# FabEEG_v5.net
KiCad netlist of a schematic drawn in EAGLE
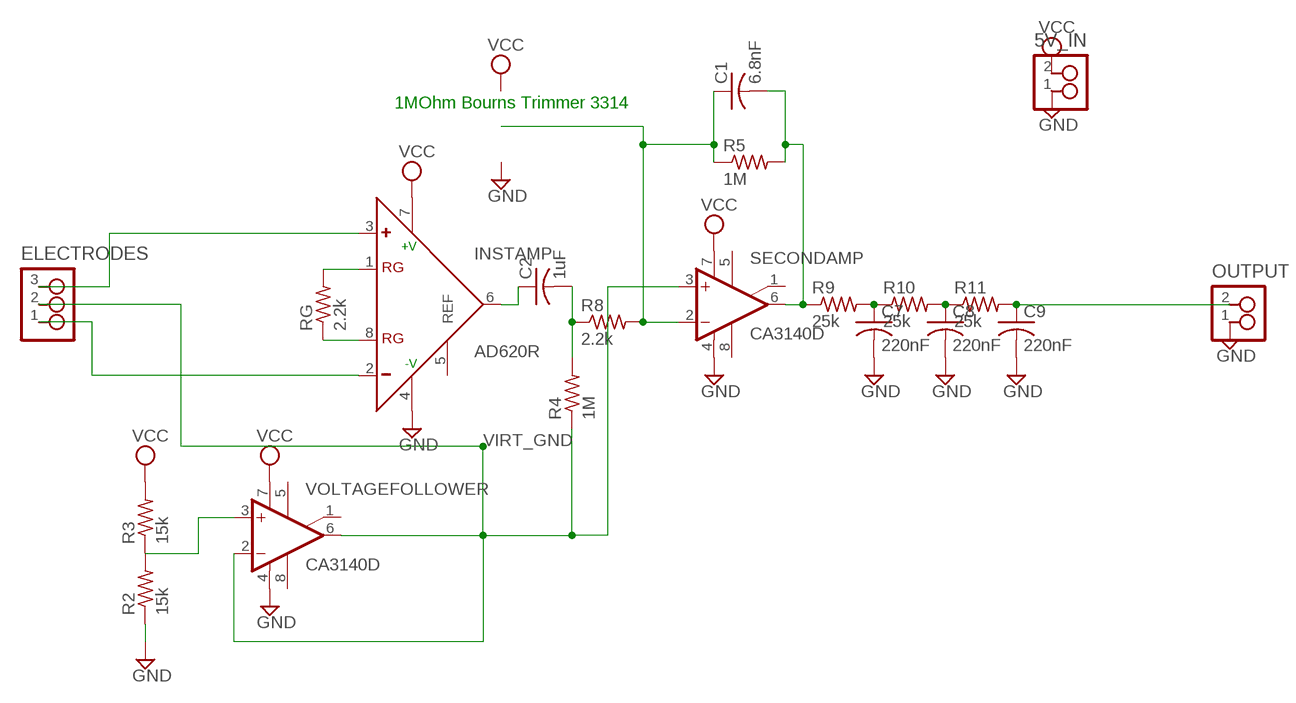
[diagram p0: schematic, sheet 1]

(export (version "E")
  (design (tool "Eeschema 10.0.6"))
  (components
    (comp (ref "5V_IN")
      (value "2_PIN_HEADERHEADER")
      (footprint "eagle-import:SMT_PINS_2")
      (libsource (lib "eagle-import") (part "2_PIN_HEADERHEADER"))
    )
    (comp (ref "C1")
      (value "6.8nF")
      (footprint "eagle-import:C1206")
      (libsource (lib "eagle-import") (part "C-USC1206"))
    )
    (comp (ref "C2")
      (value "1uF")
      (footprint "eagle-import:C1206")
      (libsource (lib "eagle-import") (part "C-USC1206"))
    )
    (comp (ref "C7")
      (value "220nF")
      (footprint "eagle-import:C1206")
      (libsource (lib "eagle-import") (part "C-USC1206"))
    )
    (comp (ref "C8")
      (value "220nF")
      (footprint "eagle-import:C1206")
      (libsource (lib "eagle-import") (part "C-USC1206"))
    )
    (comp (ref "C9")
      (value "220nF")
      (footprint "eagle-import:C1206")
      (libsource (lib "eagle-import") (part "C-USC1206"))
    )
    (comp (ref "ELECTRODES")
      (value "3_PIN_HEADERHEADER")
      (footprint "eagle-import:SMT_PINS_3")
      (libsource (lib "eagle-import") (part "3_PIN_HEADERHEADER"))
    )
    (comp (ref "INSTAMP")
      (value "AD620R")
      (footprint "eagle-import:SO8")
      (libsource (lib "eagle-import") (part "AD620R"))
    )
    (comp (ref "OUTPUT")
      (value "2_PIN_HEADERHEADER")
      (footprint "eagle-import:SMT_PINS_2")
      (libsource (lib "eagle-import") (part "2_PIN_HEADERHEADER"))
    )
    (comp (ref "R2")
      (value "15k")
      (footprint "eagle-import:R1206")
      (libsource (lib "eagle-import") (part "R-US_R1206"))
    )
    (comp (ref "R3")
      (value "15k")
      (footprint "eagle-import:R1206")
      (libsource (lib "eagle-import") (part "R-US_R1206"))
    )
    (comp (ref "R4")
      (value "1M")
      (footprint "eagle-import:R1206")
      (libsource (lib "eagle-import") (part "R-US_R1206"))
    )
    (comp (ref "R5")
      (value "1M")
      (footprint "eagle-import:R1206")
      (libsource (lib "eagle-import") (part "R-US_R1206"))
    )
    (comp (ref "R8")
      (value "2.2k")
      (footprint "eagle-import:R1206")
      (libsource (lib "eagle-import") (part "R-US_R1206"))
    )
    (comp (ref "R9")
      (value "25k")
      (footprint "eagle-import:R1206")
      (libsource (lib "eagle-import") (part "R-US_R1206"))
    )
    (comp (ref "R10")
      (value "25k")
      (footprint "eagle-import:R1206")
      (libsource (lib "eagle-import") (part "R-US_R1206"))
    )
    (comp (ref "R11")
      (value "25k")
      (footprint "eagle-import:R1206")
      (libsource (lib "eagle-import") (part "R-US_R1206"))
    )
    (comp (ref "RG")
      (value "2.2k")
      (footprint "eagle-import:R1206")
      (libsource (lib "eagle-import") (part "R-US_R1206"))
    )
    (comp (ref "SECONDAMP")
      (value "CA3140D")
      (footprint "eagle-import:SO08")
      (libsource (lib "eagle-import") (part "CA3140D"))
    )
    (comp (ref "VOLTAGEFOLLOWER")
      (value "CA3140D")
      (footprint "eagle-import:SO08")
      (libsource (lib "eagle-import") (part "CA3140D"))
    )
  )
  (nets
    (net (code "1") (name "/VIRT_GND") (class "Default")
      (node (ref "ELECTRODES") (pin "2") (pinfunction "P$2_2") (pintype "bidirectional"))
      (node (ref "R4") (pin "1") (pinfunction "1_1") (pintype "passive"))
      (node (ref "SECONDAMP") (pin "3") (pinfunction "+IN_3") (pintype "input"))
      (node (ref "VOLTAGEFOLLOWER") (pin "2") (pinfunction "-IN_2") (pintype "input"))
      (node (ref "VOLTAGEFOLLOWER") (pin "6") (pinfunction "OUT_6") (pintype "output"))
    )
    (net (code "2") (name "GND") (class "Default")
      (node (ref "5V_IN") (pin "1") (pinfunction "1_1") (pintype "bidirectional"))
      (node (ref "C7") (pin "2") (pinfunction "2_2") (pintype "passive"))
      (node (ref "C8") (pin "2") (pinfunction "2_2") (pintype "passive"))
      (node (ref "C9") (pin "2") (pinfunction "2_2") (pintype "passive"))
      (node (ref "INSTAMP") (pin "4") (pinfunction "-V_4") (pintype "power_in"))
      (node (ref "OUTPUT") (pin "1") (pinfunction "1_1") (pintype "bidirectional"))
      (node (ref "R2") (pin "1") (pinfunction "1_1") (pintype "passive"))
      (node (ref "SECONDAMP") (pin "4") (pinfunction "V-_4") (pintype "power_in"))
      (node (ref "VOLTAGEFOLLOWER") (pin "4") (pinfunction "V-_4") (pintype "power_in"))
    )
    (net (code "3") (name "Net-(C2-Pad2)") (class "Default")
      (node (ref "C2") (pin "2") (pinfunction "2_2") (pintype "passive"))
      (node (ref "R4") (pin "2") (pinfunction "2_2") (pintype "passive"))
      (node (ref "R8") (pin "1") (pinfunction "1_1") (pintype "passive"))
    )
    (net (code "4") (name "Net-(C7-Pad1)") (class "Default")
      (node (ref "C7") (pin "1") (pinfunction "1_1") (pintype "passive"))
      (node (ref "R10") (pin "1") (pinfunction "1_1") (pintype "passive"))
      (node (ref "R9") (pin "2") (pinfunction "2_2") (pintype "passive"))
    )
    (net (code "5") (name "Net-(C8-Pad1)") (class "Default")
      (node (ref "C8") (pin "1") (pinfunction "1_1") (pintype "passive"))
      (node (ref "R10") (pin "2") (pinfunction "2_2") (pintype "passive"))
      (node (ref "R11") (pin "1") (pinfunction "1_1") (pintype "passive"))
    )
    (net (code "6") (name "Net-(C9-Pad1)") (class "Default")
      (node (ref "C9") (pin "1") (pinfunction "1_1") (pintype "passive"))
      (node (ref "OUTPUT") (pin "2") (pinfunction "2_2") (pintype "bidirectional"))
      (node (ref "R11") (pin "2") (pinfunction "2_2") (pintype "passive"))
    )
    (net (code "7") (name "Net-(ELECTRODES-P$1)") (class "Default")
      (node (ref "ELECTRODES") (pin "1") (pinfunction "P$1_1") (pintype "bidirectional"))
      (node (ref "INSTAMP") (pin "2") (pinfunction "-_2") (pintype "input"))
    )
    (net (code "8") (name "Net-(ELECTRODES-P$3)") (class "Default")
      (node (ref "ELECTRODES") (pin "3") (pinfunction "P$3_3") (pintype "bidirectional"))
      (node (ref "INSTAMP") (pin "3") (pinfunction "+_3") (pintype "input"))
    )
    (net (code "9") (name "Net-(INSTAMP-OUT)") (class "Default")
      (node (ref "C2") (pin "1") (pinfunction "1_1") (pintype "passive"))
      (node (ref "INSTAMP") (pin "6") (pinfunction "OUT_6") (pintype "output"))
    )
    (net (code "10") (name "Net-(INSTAMP-RG-Pad1)") (class "Default")
      (node (ref "INSTAMP") (pin "1") (pinfunction "RG_1") (pintype "passive"))
      (node (ref "RG") (pin "2") (pinfunction "2_2") (pintype "passive"))
    )
    (net (code "11") (name "Net-(INSTAMP-RG-Pad8)") (class "Default")
      (node (ref "INSTAMP") (pin "8") (pinfunction "RG_8") (pintype "passive"))
      (node (ref "RG") (pin "1") (pinfunction "1_1") (pintype "passive"))
    )
    (net (code "12") (name "Net-(SECONDAMP--IN)") (class "Default")
      (node (ref "C1") (pin "1") (pinfunction "1_1") (pintype "passive"))
      (node (ref "R5") (pin "1") (pinfunction "1_1") (pintype "passive"))
      (node (ref "R8") (pin "2") (pinfunction "2_2") (pintype "passive"))
      (node (ref "SECONDAMP") (pin "2") (pinfunction "-IN_2") (pintype "input"))
    )
    (net (code "13") (name "Net-(SECONDAMP-OUT)") (class "Default")
      (node (ref "C1") (pin "2") (pinfunction "2_2") (pintype "passive"))
      (node (ref "R5") (pin "2") (pinfunction "2_2") (pintype "passive"))
      (node (ref "R9") (pin "1") (pinfunction "1_1") (pintype "passive"))
      (node (ref "SECONDAMP") (pin "6") (pinfunction "OUT_6") (pintype "output"))
    )
    (net (code "14") (name "Net-(VOLTAGEFOLLOWER-+IN)") (class "Default")
      (node (ref "R2") (pin "2") (pinfunction "2_2") (pintype "passive"))
      (node (ref "R3") (pin "1") (pinfunction "1_1") (pintype "passive"))
      (node (ref "VOLTAGEFOLLOWER") (pin "3") (pinfunction "+IN_3") (pintype "input"))
    )
    (net (code "15") (name "VCC") (class "Default")
      (node (ref "5V_IN") (pin "2") (pinfunction "2_2") (pintype "bidirectional"))
      (node (ref "INSTAMP") (pin "7") (pinfunction "+V_7") (pintype "power_in"))
      (node (ref "R3") (pin "2") (pinfunction "2_2") (pintype "passive"))
      (node (ref "SECONDAMP") (pin "7") (pinfunction "V+_7") (pintype "power_in"))
      (node (ref "VOLTAGEFOLLOWER") (pin "7") (pinfunction "V+_7") (pintype "power_in"))
    )
    (net (code "16") (name "unconnected-(INSTAMP-REF-Pad5)") (class "Default")
      (node (ref "INSTAMP") (pin "5") (pinfunction "REF_5") (pintype "passive"))
    )
    (net (code "17") (name "unconnected-(SECONDAMP-CMP-Pad8)") (class "Default")
      (node (ref "SECONDAMP") (pin "8") (pinfunction "CMP_8") (pintype "passive"))
    )
    (net (code "18") (name "unconnected-(SECONDAMP-ON-Pad5)") (class "Default")
      (node (ref "SECONDAMP") (pin "5") (pinfunction "ON_5") (pintype "passive"))
    )
    (net (code "19") (name "unconnected-(SECONDAMP-ON{slash}CMP-Pad1)") (class "Default")
      (node (ref "SECONDAMP") (pin "1") (pinfunction "ON/CMP_1") (pintype "passive"))
    )
    (net (code "20") (name "unconnected-(VOLTAGEFOLLOWER-CMP-Pad8)") (class "Default")
      (node (ref "VOLTAGEFOLLOWER") (pin "8") (pinfunction "CMP_8") (pintype "passive"))
    )
    (net (code "21") (name "unconnected-(VOLTAGEFOLLOWER-ON-Pad5)") (class "Default")
      (node (ref "VOLTAGEFOLLOWER") (pin "5") (pinfunction "ON_5") (pintype "passive"))
    )
    (net (code "22") (name "unconnected-(VOLTAGEFOLLOWER-ON{slash}CMP-Pad1)") (class "Default")
      (node (ref "VOLTAGEFOLLOWER") (pin "1") (pinfunction "ON/CMP_1") (pintype "passive"))
    )
  )
)
